# Schematic.net
KiCad netlist of a schematic drawn in Altium Designer
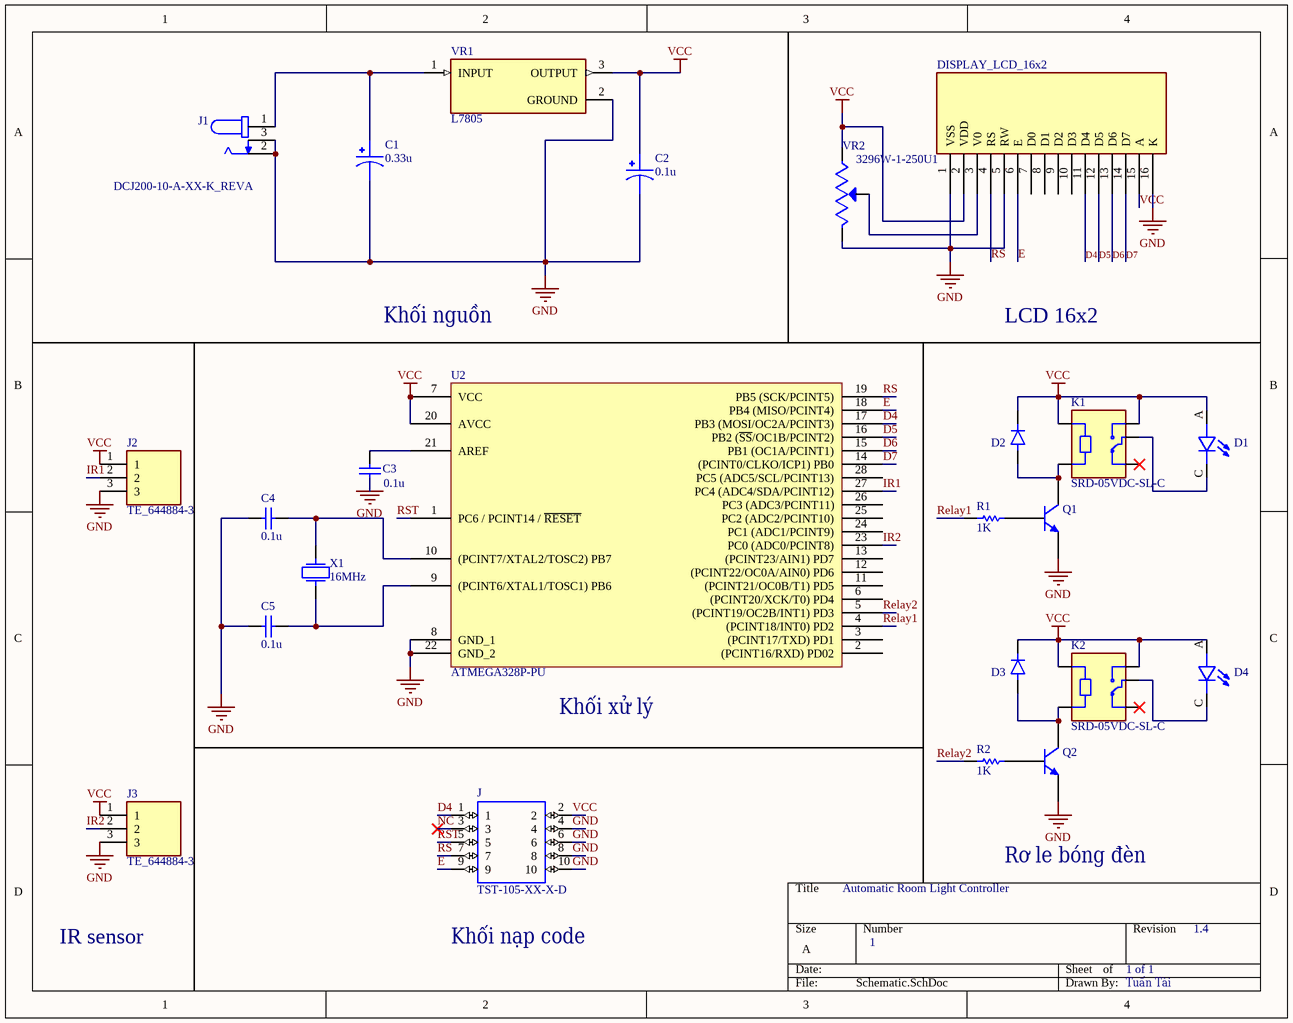
[diagram p0: Schematic.SchDoc]

(export (version "E")
  (design (tool "Eeschema 10.0.6"))
  (components
    (comp (ref "C1")
      (value "0.33u")
      (footprint "CAPPRD500W60D1330H2700")
      (description "4700ÂµF 10V Aluminum Electrolytic Capacitors Radial, Can 98.8mOhm @ 120Hz 2000 Hrs @ 85Â°C")
      (fields (field (name "MP") "478CKS010M") (field (name "MF") "Illinois Capacitor"))
      (libsource (lib "478CKS010M") (part "478CKS010M"))
    )
    (comp (ref "C2")
      (value "0.1u")
      (footprint "CAPPRD500W60D1330H2700")
      (description "4700ÂµF 10V Aluminum Electrolytic Capacitors Radial, Can 98.8mOhm @ 120Hz 2000 Hrs @ 85Â°C")
      (fields (field (name "MP") "478CKS010M") (field (name "MF") "Illinois Capacitor"))
      (libsource (lib "478CKS010M") (part "478CKS010M"))
    )
    (comp (ref "C3")
      (value "0.1u")
      (footprint "CAPPRD500W60D1330H2700")
      (description "Capacitor")
      (libsource (lib "Simulation Generic Components") (part "Capacitor"))
    )
    (comp (ref "C4")
      (value "0.1u")
      (footprint "CAPPRD500W60D1330H2700")
      (description "Capacitor")
      (libsource (lib "Simulation Generic Components") (part "Capacitor"))
    )
    (comp (ref "C5")
      (value "0.1u")
      (footprint "CAPPRD500W60D1330H2700")
      (description "Capacitor")
      (libsource (lib "Simulation Generic Components") (part "Capacitor"))
    )
    (comp (ref "D1")
      (value "L08R5000Q1")
      (footprint "LEDRD254W57D500H1070")
      (fields (field (name "MF") "LED Technology"))
      (libsource (lib "L08R5000Q1") (part "L08R5000Q1"))
    )
    (comp (ref "D2")
      (value "1N4007-T")
      (footprint "DIOAD780W78L463D236")
      (description "Diode Standard 1A 1000V 1Vf DO41 ¦ Diodes Inc 1N4007-T")
      (fields (field (name "MF") "Diodes Incorporated"))
      (libsource (lib "1N4007-T") (part "1N4007-T"))
    )
    (comp (ref "D3")
      (value "1N4007-T")
      (footprint "DIOAD780W78L463D236")
      (description "Diode Standard 1A 1000V 1Vf DO41 ¦ Diodes Inc 1N4007-T")
      (fields (field (name "MF") "Diodes Incorporated"))
      (libsource (lib "1N4007-T") (part "1N4007-T"))
    )
    (comp (ref "D4")
      (value "L08R5000Q1")
      (footprint "LEDRD254W57D500H1070")
      (fields (field (name "MF") "LED Technology"))
      (libsource (lib "L08R5000Q1") (part "L08R5000Q1"))
    )
    (comp (ref "J")
      (value "TST-105-XX-X-D")
      (footprint "TST-105-XX-X-D")
      (description "Connector Header Through Hole 10 position 0.100 _2.54mm_")
      (fields (field (name "MF") "Samtec") (field (name "MP") "TST-105-02-F-D"))
      (libsource (lib "SnapEDAsch") (part "TST-105-XX-X-D"))
    )
    (comp (ref "J1")
      (value "DCJ200-10-A-XX-K_REVA")
      (footprint "GCT_DCJ200-10-A-XX-K_REVA")
      (description "Power Barrel Connector Jack 2.05mm ID (0.081), 5.50mm OD (0.217) Through Hole, Right Angle")
      (fields (field (name "MF") "Global Connector Technology") (field (name "MP") "DCJ200-10-A-K1-K"))
      (libsource (lib "DCJ200-10-A-XX-K_REVA") (part "DCJ200-10-A-XX-K_REVA"))
    )
    (comp (ref "J2")
      (value "TE_644884-3")
      (footprint "TE_644884-3")
      (fields (field (name "MP") "644884-3"))
      (libsource (lib "644884-3") (part "644884-3"))
    )
    (comp (ref "J3")
      (value "TE_644884-3")
      (footprint "TE_644884-3")
      (fields (field (name "MP") "644884-3"))
      (libsource (lib "644884-3") (part "644884-3"))
    )
    (comp (ref "K1")
      (value "SRD-05VDC-SL-C")
      (footprint "RELAY_SRD-05VDC-SL-C")
      (fields (field (name "MF") "Songle Relay"))
      (libsource (lib "SRD-05VDC-SL-C") (part "SRD-05VDC-SL-C"))
    )
    (comp (ref "K2")
      (value "SRD-05VDC-SL-C")
      (footprint "RELAY_SRD-05VDC-SL-C")
      (fields (field (name "MF") "Songle Relay"))
      (libsource (lib "SRD-05VDC-SL-C") (part "SRD-05VDC-SL-C"))
    )
    (comp (ref "Q1")
      (value "Bipolar NPN 3 Pins Transistor VBIC Model")
      (footprint "TO92")
      (libsource (lib "Simulation Generic Components") (part "BJT NPN VBIC"))
    )
    (comp (ref "Q2")
      (value "Bipolar NPN 3 Pins Transistor VBIC Model")
      (footprint "TO92")
      (libsource (lib "Simulation Generic Components") (part "BJT NPN VBIC"))
    )
    (comp (ref "R1")
      (value "1K")
      (footprint "RESAD1100W55L680D260")
      (description "Resistor")
      (libsource (lib "Simulation Generic Components") (part "Resistor"))
    )
    (comp (ref "R2")
      (value "1K")
      (footprint "RESAD1100W55L680D260")
      (description "Resistor")
      (libsource (lib "Simulation Generic Components") (part "Resistor"))
    )
    (comp (ref "U1")
      (value "DISPLAY_LCD_16x2")
      (footprint "DISPLAY_LCD_16_2")
      (description "Display LCD 16x2 I2C.")
      (libsource (lib "Displays") (part "DISPLAY_LCD_16_2"))
    )
    (comp (ref "U2")
      (value "ATMEGA328P-PU")
      (footprint "27_DIP_7.62mm")
      (description "ATMEGA328P-PU; 8 bit Microcontroller AVR 20MHz 1; 32kb Flash; 2kb RAM; I2C SPI 2")
      (fields (field (name "MANUFACTURER") "Microchip / Atmel"))
      (libsource (lib "ATMEGA328P-PU") (part "ATMEGA328P-PU"))
    )
    (comp (ref "VR1")
      (value "L7805")
      (footprint "TO255P1020X450X2000-3")
      (description "Standard Regulator Pos 5V 1.5A 3-Pin(3+Tab) TO-220FP Tube")
      (fields (field (name "MF") "STMicroelectronics"))
      (libsource (lib "L7805") (part "L7805"))
    )
    (comp (ref "VR2")
      (value "3296W-1-250")
      (footprint "TRIM_3296W-1-250")
      (description "25 Ohms 0.5W, 1/2W PC Pins Through Hole Trimmer Potentiometer Cermet 25.0 Turn Top Adjustment")
      (fields (field (name "MF") "Bourns"))
      (libsource (lib "3296W-1-250") (part "3296W-1-250"))
    )
    (comp (ref "X1")
      (value "Crystal")
      (footprint "XTAL_HC49P488W46L1150T500H350")
      (fields (field (name "F0") "16MHz"))
      (libsource (lib "Simulation Generic Components") (part "Crystal"))
    )
  )
  (nets
    (net (code "1") (name "/D4") (class "Default")
      (node (ref "J") (pin "1") (pinfunction "1_1") (pintype "bidirectional"))
      (node (ref "U1") (pin "11") (pinfunction "D4_11") (pintype "passive"))
      (node (ref "U2") (pin "17") (pinfunction "PB3_(MOSI/OC2A/PCINT3)_17") (pintype "passive"))
    )
    (net (code "2") (name "/D5") (class "Default")
      (node (ref "U1") (pin "12") (pinfunction "D5_12") (pintype "passive"))
      (node (ref "U2") (pin "16") (pinfunction "PB2_(~{SS}/OC1B/PCINT2)_16") (pintype "passive"))
    )
    (net (code "3") (name "/D6") (class "Default")
      (node (ref "U1") (pin "13") (pinfunction "D6_13") (pintype "passive"))
      (node (ref "U2") (pin "15") (pinfunction "PB1_(OC1A/PCINT1)_15") (pintype "passive"))
    )
    (net (code "4") (name "/D7") (class "Default")
      (node (ref "U1") (pin "14") (pinfunction "D7_14") (pintype "passive"))
      (node (ref "U2") (pin "14") (pinfunction "(PCINT0/CLKO/ICP1)_PB0_14") (pintype "passive"))
    )
    (net (code "5") (name "/E") (class "Default")
      (node (ref "J") (pin "9") (pinfunction "9_9") (pintype "bidirectional"))
      (node (ref "U1") (pin "6") (pinfunction "E_6") (pintype "passive"))
      (node (ref "U2") (pin "18") (pinfunction "PB4_(MISO/PCINT4)_18") (pintype "passive"))
    )
    (net (code "6") (name "/IR1") (class "Default")
      (node (ref "J2") (pin "2") (pinfunction "2_2") (pintype "passive"))
      (node (ref "U2") (pin "27") (pinfunction "PC4_(ADC4/SDA/PCINT12)_27") (pintype "passive"))
    )
    (net (code "7") (name "/IR2") (class "Default")
      (node (ref "J3") (pin "2") (pinfunction "2_2") (pintype "passive"))
      (node (ref "U2") (pin "23") (pinfunction "PC0_(ADC0/PCINT8)_23") (pintype "passive"))
    )
    (net (code "8") (name "/NC") (class "Default")
      (node (ref "J") (pin "3") (pinfunction "3_3") (pintype "bidirectional+no_connect"))
    )
    (net (code "9") (name "/RS") (class "Default")
      (node (ref "J") (pin "7") (pinfunction "7_7") (pintype "bidirectional"))
      (node (ref "U1") (pin "4") (pinfunction "RS_4") (pintype "passive"))
      (node (ref "U2") (pin "19") (pinfunction "PB5_(SCK/PCINT5)_19") (pintype "passive"))
    )
    (net (code "10") (name "/RST") (class "Default")
      (node (ref "J") (pin "5") (pinfunction "5_5") (pintype "bidirectional"))
      (node (ref "U2") (pin "1") (pinfunction "PC6_/_PCINT14_/_~{RESET}_1") (pintype "passive"))
    )
    (net (code "11") (name "/Relay1") (class "Default")
      (node (ref "R1") (pin "1") (pinfunction "1_1") (pintype "passive"))
      (node (ref "U2") (pin "4") (pinfunction "(PCINT18/INT0)_PD2_4") (pintype "passive"))
    )
    (net (code "12") (name "/Relay2") (class "Default")
      (node (ref "R2") (pin "1") (pinfunction "1_1") (pintype "passive"))
      (node (ref "U2") (pin "5") (pinfunction "(PCINT19/OC2B/INT1)_PD3_5") (pintype "passive"))
    )
    (net (code "13") (name "GND") (class "Default")
      (node (ref "C1") (pin "2") (pinfunction "2_2") (pintype "passive"))
      (node (ref "C2") (pin "2") (pinfunction "2_2") (pintype "passive"))
      (node (ref "C3") (pin "1") (pinfunction "1_1") (pintype "passive"))
      (node (ref "C4") (pin "1") (pinfunction "1_1") (pintype "passive"))
      (node (ref "C5") (pin "1") (pinfunction "1_1") (pintype "passive"))
      (node (ref "J") (pin "10") (pinfunction "10_10") (pintype "bidirectional"))
      (node (ref "J") (pin "4") (pinfunction "4_4") (pintype "bidirectional"))
      (node (ref "J") (pin "6") (pinfunction "6_6") (pintype "bidirectional"))
      (node (ref "J") (pin "8") (pinfunction "8_8") (pintype "bidirectional"))
      (node (ref "J1") (pin "2") (pinfunction "2_2") (pintype "passive"))
      (node (ref "J1") (pin "3") (pinfunction "3_3") (pintype "passive"))
      (node (ref "J2") (pin "3") (pinfunction "3_3") (pintype "passive"))
      (node (ref "J3") (pin "3") (pinfunction "3_3") (pintype "passive"))
      (node (ref "Q1") (pin "3") (pinfunction "E_3") (pintype "passive"))
      (node (ref "Q2") (pin "3") (pinfunction "E_3") (pintype "passive"))
      (node (ref "U1") (pin "1") (pinfunction "VSS_1") (pintype "passive"))
      (node (ref "U1") (pin "16") (pinfunction "K_16") (pintype "passive"))
      (node (ref "U1") (pin "5") (pinfunction "RW_5") (pintype "passive"))
      (node (ref "U2") (pin "22") (pinfunction "GND_2_22") (pintype "passive"))
      (node (ref "U2") (pin "8") (pinfunction "GND_1_8") (pintype "passive"))
      (node (ref "VR1") (pin "2") (pinfunction "GROUND_2") (pintype "power_in"))
      (node (ref "VR2") (pin "3") (pinfunction "CW_3") (pintype "passive"))
    )
    (net (code "14") (name "Net-(D1-PadC)") (class "Default")
      (node (ref "D1") (pin "C") (pinfunction "C_C") (pintype "passive"))
      (node (ref "K1") (pin "COM") (pinfunction "COM_COM") (pintype "passive"))
    )
    (net (code "15") (name "Net-(D4-PadC)") (class "Default")
      (node (ref "D4") (pin "C") (pinfunction "C_C") (pintype "passive"))
      (node (ref "K2") (pin "COM") (pinfunction "COM_COM") (pintype "passive"))
    )
    (net (code "16") (name "Net-(Q1-B)") (class "Default")
      (node (ref "Q1") (pin "2") (pinfunction "B_2") (pintype "passive"))
      (node (ref "R1") (pin "2") (pinfunction "2_2") (pintype "passive"))
    )
    (net (code "17") (name "Net-(Q1-C)") (class "Default")
      (node (ref "D2") (pin "A") (pinfunction "A_A") (pintype "passive"))
      (node (ref "K1") (pin "A2") (pinfunction "A2_A2") (pintype "passive"))
      (node (ref "Q1") (pin "1") (pinfunction "C_1") (pintype "passive"))
    )
    (net (code "18") (name "Net-(Q2-B)") (class "Default")
      (node (ref "Q2") (pin "2") (pinfunction "B_2") (pintype "passive"))
      (node (ref "R2") (pin "2") (pinfunction "2_2") (pintype "passive"))
    )
    (net (code "19") (name "Net-(Q2-C)") (class "Default")
      (node (ref "D3") (pin "A") (pinfunction "A_A") (pintype "passive"))
      (node (ref "K2") (pin "A2") (pinfunction "A2_A2") (pintype "passive"))
      (node (ref "Q2") (pin "1") (pinfunction "C_1") (pintype "passive"))
    )
    (net (code "20") (name "Net-(U1-V0)") (class "Default")
      (node (ref "U1") (pin "3") (pinfunction "V0_3") (pintype "passive"))
      (node (ref "VR2") (pin "2") (pinfunction "WIPER_2") (pintype "passive"))
    )
    (net (code "21") (name "Net-(U2-(PCINT6{slash}XTAL1{slash}TOSC1)_PB6)") (class "Default")
      (node (ref "C5") (pin "2") (pinfunction "2_2") (pintype "passive"))
      (node (ref "U2") (pin "9") (pinfunction "(PCINT6/XTAL1/TOSC1)_PB6_9") (pintype "passive"))
      (node (ref "X1") (pin "1") (pinfunction "1_1") (pintype "passive"))
    )
    (net (code "22") (name "Net-(U2-(PCINT7{slash}XTAL2{slash}TOSC2)_PB7)") (class "Default")
      (node (ref "C4") (pin "2") (pinfunction "2_2") (pintype "passive"))
      (node (ref "U2") (pin "10") (pinfunction "(PCINT7/XTAL2/TOSC2)_PB7_10") (pintype "passive"))
      (node (ref "X1") (pin "2") (pinfunction "2_2") (pintype "passive"))
    )
    (net (code "23") (name "Net-(U2-AREF)") (class "Default")
      (node (ref "C3") (pin "2") (pinfunction "2_2") (pintype "passive"))
      (node (ref "U2") (pin "21") (pinfunction "AREF_21") (pintype "passive"))
    )
    (net (code "24") (name "Net-(VR1-INPUT)") (class "Default")
      (node (ref "C1") (pin "1") (pinfunction "1_1") (pintype "passive"))
      (node (ref "J1") (pin "1") (pinfunction "1_1") (pintype "passive"))
      (node (ref "VR1") (pin "1") (pinfunction "INPUT_1") (pintype "input"))
    )
    (net (code "25") (name "VCC") (class "Default")
      (node (ref "C2") (pin "1") (pinfunction "1_1") (pintype "passive"))
      (node (ref "D1") (pin "A") (pinfunction "A_A") (pintype "passive"))
      (node (ref "D2") (pin "K") (pinfunction "K_K") (pintype "passive"))
      (node (ref "D3") (pin "K") (pinfunction "K_K") (pintype "passive"))
      (node (ref "D4") (pin "A") (pinfunction "A_A") (pintype "passive"))
      (node (ref "J") (pin "2") (pinfunction "2_2") (pintype "bidirectional"))
      (node (ref "J2") (pin "1") (pinfunction "1_1") (pintype "passive"))
      (node (ref "J3") (pin "1") (pinfunction "1_1") (pintype "passive"))
      (node (ref "K1") (pin "A1") (pinfunction "A1_A1") (pintype "passive"))
      (node (ref "K1") (pin "NO") (pinfunction "NO_NO") (pintype "passive"))
      (node (ref "K2") (pin "A1") (pinfunction "A1_A1") (pintype "passive"))
      (node (ref "K2") (pin "NO") (pinfunction "NO_NO") (pintype "passive"))
      (node (ref "U1") (pin "15") (pinfunction "A_15") (pintype "passive"))
      (node (ref "U1") (pin "2") (pinfunction "VDD_2") (pintype "passive"))
      (node (ref "U2") (pin "20") (pinfunction "AVCC_20") (pintype "passive"))
      (node (ref "U2") (pin "7") (pinfunction "VCC_7") (pintype "passive"))
      (node (ref "VR1") (pin "3") (pinfunction "OUTPUT_3") (pintype "output"))
      (node (ref "VR2") (pin "1") (pinfunction "CCW_1") (pintype "passive"))
    )
    (net (code "26") (name "unconnected-(K1-PadNC)") (class "Default")
      (node (ref "K1") (pin "NC") (pinfunction "NC_NC") (pintype "passive+no_connect"))
    )
    (net (code "27") (name "unconnected-(K2-PadNC)") (class "Default")
      (node (ref "K2") (pin "NC") (pinfunction "NC_NC") (pintype "passive+no_connect"))
    )
    (net (code "28") (name "unconnected-(U1-D0-Pad7)") (class "Default")
      (node (ref "U1") (pin "7") (pinfunction "D0_7") (pintype "passive"))
    )
    (net (code "29") (name "unconnected-(U1-D1-Pad8)") (class "Default")
      (node (ref "U1") (pin "8") (pinfunction "D1_8") (pintype "passive"))
    )
    (net (code "30") (name "unconnected-(U1-D2-Pad9)") (class "Default")
      (node (ref "U1") (pin "9") (pinfunction "D2_9") (pintype "passive"))
    )
    (net (code "31") (name "unconnected-(U1-D3-Pad10)") (class "Default")
      (node (ref "U1") (pin "10") (pinfunction "D3_10") (pintype "passive"))
    )
    (net (code "32") (name "unconnected-(U2-(PCINT16{slash}RXD)_PD02-Pad2)") (class "Default")
      (node (ref "U2") (pin "2") (pinfunction "(PCINT16/RXD)_PD02_2") (pintype "passive"))
    )
    (net (code "33") (name "unconnected-(U2-(PCINT17{slash}TXD)_PD1-Pad3)") (class "Default")
      (node (ref "U2") (pin "3") (pinfunction "(PCINT17/TXD)_PD1_3") (pintype "passive"))
    )
    (net (code "34") (name "unconnected-(U2-(PCINT20{slash}XCK{slash}T0)_PD4-Pad6)") (class "Default")
      (node (ref "U2") (pin "6") (pinfunction "(PCINT20/XCK/T0)_PD4_6") (pintype "passive"))
    )
    (net (code "35") (name "unconnected-(U2-(PCINT21{slash}OC0B{slash}T1)_PD5-Pad11)") (class "Default")
      (node (ref "U2") (pin "11") (pinfunction "(PCINT21/OC0B/T1)_PD5_11") (pintype "passive"))
    )
    (net (code "36") (name "unconnected-(U2-(PCINT22{slash}OC0A{slash}AIN0)_PD6-Pad12)") (class "Default")
      (node (ref "U2") (pin "12") (pinfunction "(PCINT22/OC0A/AIN0)_PD6_12") (pintype "passive"))
    )
    (net (code "37") (name "unconnected-(U2-(PCINT23{slash}AIN1)_PD7-Pad13)") (class "Default")
      (node (ref "U2") (pin "13") (pinfunction "(PCINT23/AIN1)_PD7_13") (pintype "passive"))
    )
    (net (code "38") (name "unconnected-(U2-PC1_(ADC1{slash}PCINT9)-Pad24)") (class "Default")
      (node (ref "U2") (pin "24") (pinfunction "PC1_(ADC1/PCINT9)_24") (pintype "passive"))
    )
    (net (code "39") (name "unconnected-(U2-PC2_(ADC2{slash}PCINT10)-Pad25)") (class "Default")
      (node (ref "U2") (pin "25") (pinfunction "PC2_(ADC2/PCINT10)_25") (pintype "passive"))
    )
    (net (code "40") (name "unconnected-(U2-PC3_(ADC3{slash}PCINT11)-Pad26)") (class "Default")
      (node (ref "U2") (pin "26") (pinfunction "PC3_(ADC3/PCINT11)_26") (pintype "passive"))
    )
    (net (code "41") (name "unconnected-(U2-PC5_(ADC5{slash}SCL{slash}PCINT13)-Pad28)") (class "Default")
      (node (ref "U2") (pin "28") (pinfunction "PC5_(ADC5/SCL/PCINT13)_28") (pintype "passive"))
    )
  )
)
